# CAN.net
KiCad netlist of a schematic drawn in Altium Designer
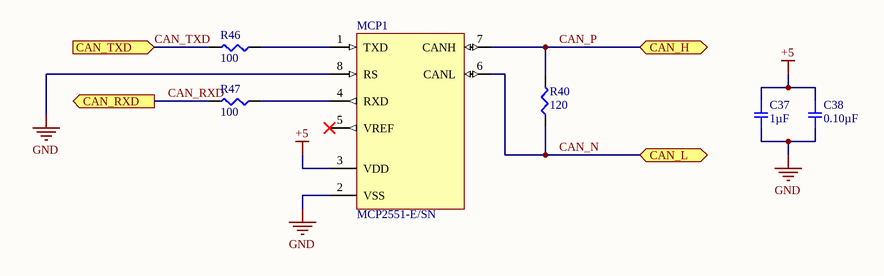
[diagram p0: CAN.SchDoc]

(export (version "E")
  (design (tool "Eeschema 10.0.6"))
  (components
    (comp (ref "C37")
      (value "1µF")
      (footprint "0805")
      (description "CAP CER 1.0UF 16V X7R 0805")
      (fields
        (field (name "DIGI-KEY PART NUMBER") "490-12590-1-ND")
        (field (name "PART NUMBER") "GCM219R71C105KA37J")
      )
      (libsource (lib "Cap_805") (part "GCM219R71C105KA37J"))
    )
    (comp (ref "C38")
      (value "0.10µF")
      (footprint "0805")
      (description "CAP CER 0.1UF 25V X7R 0805")
      (fields
        (field (name "DIGI-KEY PART NUMBER") "490-12754-1-ND")
        (field (name "PART NUMBER") "GRM219R71E104KA01D")
      )
      (libsource (lib "Cap_805") (part "GRM219R71E104KA01D"))
    )
    (comp (ref "MCP1")
      (value "MCP2551-E/SN")
      (footprint "SOIC-SN8_N")
      (description "High-Speed CAN Transceiver, 8-Pin SOIC, Extended Temperature")
      (fields (field (name "MANUFACTURER") "Microchip"))
      (libsource (lib "Microchip Interface") (part "MCP2551-E/SN"))
    )
    (comp (ref "R40")
      (value "120")
      (footprint "0805")
      (description "RES SMD 120 OHM 5% 1/8W 0805")
      (fields (field (name "PART NUMBER") "ERJ-6GEYJ121V") (field (name "DIGI-KEY PART NUMBER") "P120ACT-ND"))
      (libsource (lib "Res_805") (part "ERJ-6GEYJ121V"))
    )
    (comp (ref "R46")
      (value "100")
      (footprint "0805")
      (description "RES SMD 120 OHM 5% 1/8W 0805")
      (fields (field (name "PART NUMBER") "ERJ-6GEYJ121V") (field (name "DIGI-KEY PART NUMBER") "P120ACT-ND"))
      (libsource (lib "Res_805") (part "ERJ-6GEYJ121V"))
    )
    (comp (ref "R47")
      (value "100")
      (footprint "0805")
      (description "RES SMD 120 OHM 5% 1/8W 0805")
      (fields (field (name "PART NUMBER") "ERJ-6GEYJ121V") (field (name "DIGI-KEY PART NUMBER") "P120ACT-ND"))
      (libsource (lib "Res_805") (part "ERJ-6GEYJ121V"))
    )
  )
  (nets
    (net (code "1") (name "+5") (class "Default")
      (node (ref "C37") (pin "1") (pinfunction "1_1") (pintype "passive"))
      (node (ref "C38") (pin "1") (pinfunction "1_1") (pintype "passive"))
      (node (ref "MCP1") (pin "3") (pinfunction "VDD_3") (pintype "power_in"))
    )
    (net (code "2") (name "/CAN_N") (class "Default")
      (node (ref "MCP1") (pin "6") (pinfunction "CANL_6") (pintype "bidirectional"))
      (node (ref "R40") (pin "1") (pinfunction "1_1") (pintype "passive"))
    )
    (net (code "3") (name "/CAN_P") (class "Default")
      (node (ref "MCP1") (pin "7") (pinfunction "CANH_7") (pintype "bidirectional"))
      (node (ref "R40") (pin "2") (pinfunction "2_2") (pintype "passive"))
    )
    (net (code "4") (name "/CAN_RXD") (class "Default")
      (node (ref "R47") (pin "2") (pinfunction "2_2") (pintype "passive"))
    )
    (net (code "5") (name "/CAN_TXD") (class "Default")
      (node (ref "R46") (pin "2") (pinfunction "2_2") (pintype "passive"))
    )
    (net (code "6") (name "GND") (class "Default")
      (node (ref "C37") (pin "2") (pinfunction "2_2") (pintype "passive"))
      (node (ref "C38") (pin "2") (pinfunction "2_2") (pintype "passive"))
      (node (ref "MCP1") (pin "2") (pinfunction "VSS_2") (pintype "power_in"))
      (node (ref "MCP1") (pin "8") (pinfunction "RS_8") (pintype "input"))
    )
    (net (code "7") (name "Net-(MCP1-RXD)") (class "Default")
      (node (ref "MCP1") (pin "4") (pinfunction "RXD_4") (pintype "output"))
      (node (ref "R47") (pin "1") (pinfunction "1_1") (pintype "passive"))
    )
    (net (code "8") (name "Net-(MCP1-TXD)") (class "Default")
      (node (ref "MCP1") (pin "1") (pinfunction "TXD_1") (pintype "input"))
      (node (ref "R46") (pin "1") (pinfunction "1_1") (pintype "passive"))
    )
    (net (code "9") (name "unconnected-(MCP1-VREF-Pad5)") (class "Default")
      (node (ref "MCP1") (pin "5") (pinfunction "VREF_5") (pintype "output+no_connect"))
    )
  )
)
